# Adafruit_NeoTrellis_4x4.net
KiCad netlist of a schematic drawn in EAGLE
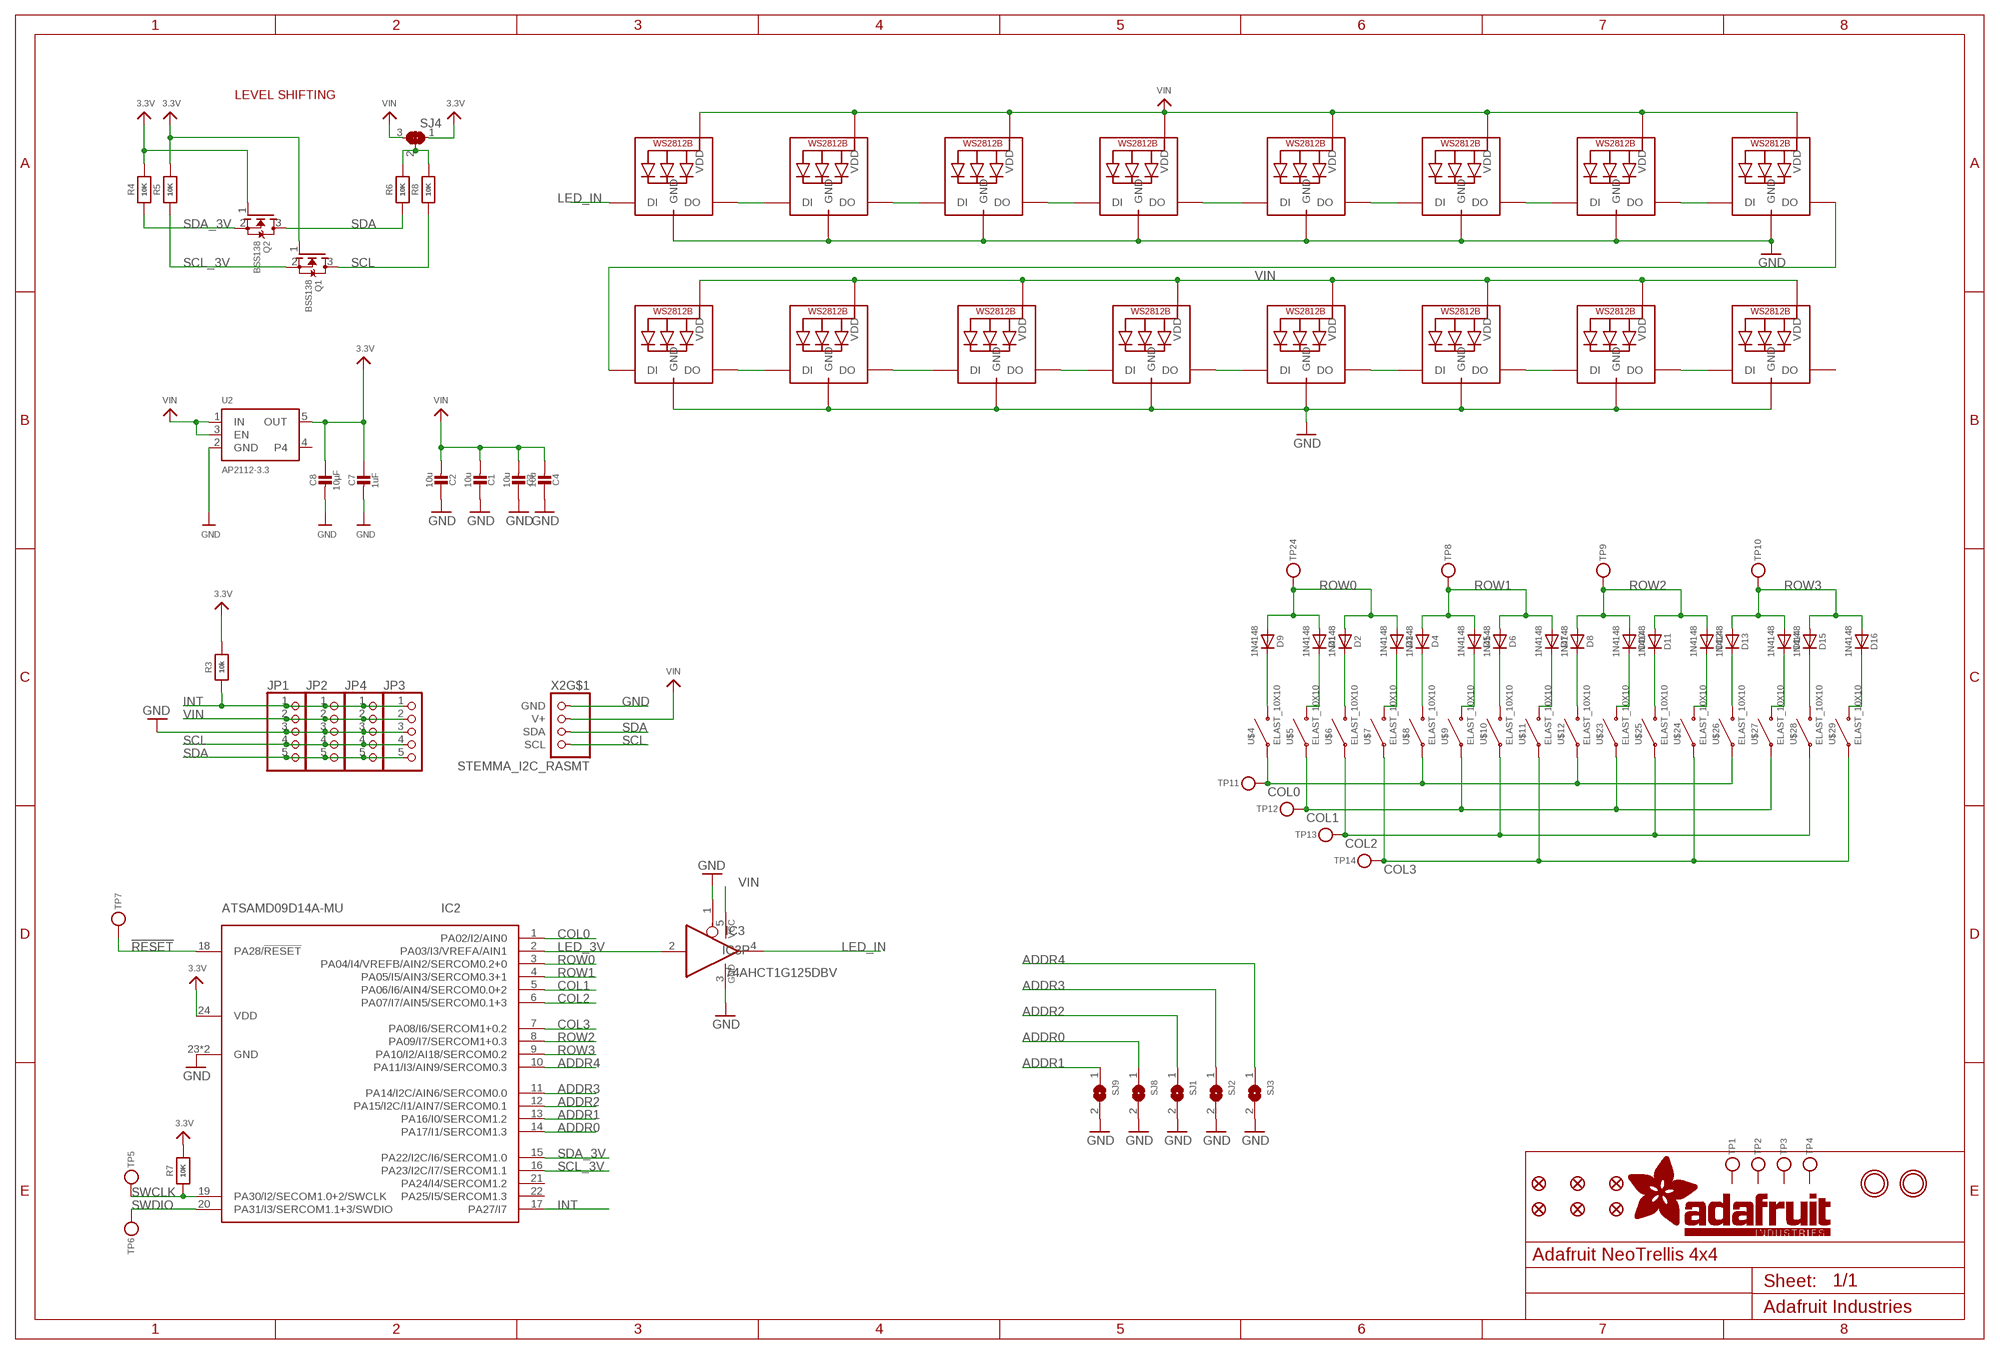
[diagram p0: schematic, sheet 1]

(export (version "E")
  (design (tool "Eeschema 10.0.6"))
  (components
    (comp (ref "C1")
      (value "10u")
      (footprint "eagle-import:0805-NO")
      (libsource (lib "eagle-import") (part "CAP_CERAMIC0805-NOOUTLINE"))
    )
    (comp (ref "C2")
      (value "10u")
      (footprint "eagle-import:0805-NO")
      (libsource (lib "eagle-import") (part "CAP_CERAMIC0805-NOOUTLINE"))
    )
    (comp (ref "C3")
      (value "10u")
      (footprint "eagle-import:0805-NO")
      (libsource (lib "eagle-import") (part "CAP_CERAMIC0805-NOOUTLINE"))
    )
    (comp (ref "C4")
      (value "10u")
      (footprint "eagle-import:0805-NO")
      (libsource (lib "eagle-import") (part "CAP_CERAMIC0805-NOOUTLINE"))
    )
    (comp (ref "C7")
      (value "1uF")
      (footprint "eagle-import:0603-NO")
      (libsource (lib "eagle-import") (part "CAP_CERAMIC0603_NO"))
    )
    (comp (ref "C8")
      (value "10µF")
      (footprint "eagle-import:0805-NO")
      (libsource (lib "eagle-import") (part "CAP_CERAMIC0805-NOOUTLINE"))
    )
    (comp (ref "D1")
      (value "1N4148")
      (footprint "eagle-import:SOD-323")
      (libsource (lib "eagle-import") (part "DIODESOD-323"))
    )
    (comp (ref "D2")
      (value "1N4148")
      (footprint "eagle-import:SOD-323")
      (libsource (lib "eagle-import") (part "DIODESOD-323"))
    )
    (comp (ref "D3")
      (value "1N4148")
      (footprint "eagle-import:SOD-323")
      (libsource (lib "eagle-import") (part "DIODESOD-323"))
    )
    (comp (ref "D4")
      (value "1N4148")
      (footprint "eagle-import:SOD-323")
      (libsource (lib "eagle-import") (part "DIODESOD-323"))
    )
    (comp (ref "D5")
      (value "1N4148")
      (footprint "eagle-import:SOD-323")
      (libsource (lib "eagle-import") (part "DIODESOD-323"))
    )
    (comp (ref "D6")
      (value "1N4148")
      (footprint "eagle-import:SOD-323")
      (libsource (lib "eagle-import") (part "DIODESOD-323"))
    )
    (comp (ref "D7")
      (value "1N4148")
      (footprint "eagle-import:SOD-323")
      (libsource (lib "eagle-import") (part "DIODESOD-323"))
    )
    (comp (ref "D8")
      (value "1N4148")
      (footprint "eagle-import:SOD-323")
      (libsource (lib "eagle-import") (part "DIODESOD-323"))
    )
    (comp (ref "D9")
      (value "1N4148")
      (footprint "eagle-import:SOD-323")
      (libsource (lib "eagle-import") (part "DIODESOD-323"))
    )
    (comp (ref "D10")
      (value "1N4148")
      (footprint "eagle-import:SOD-323")
      (libsource (lib "eagle-import") (part "DIODESOD-323"))
    )
    (comp (ref "D11")
      (value "1N4148")
      (footprint "eagle-import:SOD-323")
      (libsource (lib "eagle-import") (part "DIODESOD-323"))
    )
    (comp (ref "D12")
      (value "1N4148")
      (footprint "eagle-import:SOD-323")
      (libsource (lib "eagle-import") (part "DIODESOD-323"))
    )
    (comp (ref "D13")
      (value "1N4148")
      (footprint "eagle-import:SOD-323")
      (libsource (lib "eagle-import") (part "DIODESOD-323"))
    )
    (comp (ref "D14")
      (value "1N4148")
      (footprint "eagle-import:SOD-323")
      (libsource (lib "eagle-import") (part "DIODESOD-323"))
    )
    (comp (ref "D15")
      (value "1N4148")
      (footprint "eagle-import:SOD-323")
      (libsource (lib "eagle-import") (part "DIODESOD-323"))
    )
    (comp (ref "D16")
      (value "1N4148")
      (footprint "eagle-import:SOD-323")
      (libsource (lib "eagle-import") (part "DIODESOD-323"))
    )
    (comp (ref "FID1")
      (value "FIDUCIAL_1MM")
      (footprint "eagle-import:FIDUCIAL_1MM")
      (libsource (lib "eagle-import") (part "FIDUCIAL_1MM"))
    )
    (comp (ref "FID2")
      (value "FIDUCIAL_1MM")
      (footprint "eagle-import:FIDUCIAL_1MM")
      (libsource (lib "eagle-import") (part "FIDUCIAL_1MM"))
    )
    (comp (ref "FID3")
      (value "FIDUCIAL_1MM")
      (footprint "eagle-import:FIDUCIAL_1MM")
      (libsource (lib "eagle-import") (part "FIDUCIAL_1MM"))
    )
    (comp (ref "FID4")
      (value "FIDUCIAL_1MM")
      (footprint "eagle-import:FIDUCIAL_1MM")
      (libsource (lib "eagle-import") (part "FIDUCIAL_1MM"))
    )
    (comp (ref "FID5")
      (value "FIDUCIAL_1MM")
      (footprint "eagle-import:FIDUCIAL_1MM")
      (libsource (lib "eagle-import") (part "FIDUCIAL_1MM"))
    )
    (comp (ref "FID6")
      (value "FIDUCIAL_1MM")
      (footprint "eagle-import:FIDUCIAL_1MM")
      (libsource (lib "eagle-import") (part "FIDUCIAL_1MM"))
    )
    (comp (ref "IC2")
      (value "ATSAMD09D14A-MU")
      (footprint "eagle-import:QFN24_4MM")
      (libsource (lib "eagle-import") (part "ATSAMD09D14A-MU"))
    )
    (comp (ref "IC3")
      (value "74AHCT1G125DBV")
      (footprint "eagle-import:SOT23-5")
      (libsource (lib "eagle-import") (part "741G125DBVAHCT"))
    )
    (comp (ref "JP1")
      (value "HEADER-1X5EDGESMT")
      (footprint "eagle-import:5P_EDGECONNECT")
      (libsource (lib "eagle-import") (part "HEADER-1X5EDGESMT"))
    )
    (comp (ref "JP2")
      (value "HEADER-1X5EDGESMT")
      (footprint "eagle-import:5P_EDGECONNECT")
      (libsource (lib "eagle-import") (part "HEADER-1X5EDGESMT"))
    )
    (comp (ref "JP3")
      (value "HEADER-1X5EDGESMT")
      (footprint "eagle-import:5P_EDGECONNECT")
      (libsource (lib "eagle-import") (part "HEADER-1X5EDGESMT"))
    )
    (comp (ref "JP4")
      (value "HEADER-1X5EDGESMT")
      (footprint "eagle-import:5P_EDGECONNECT")
      (libsource (lib "eagle-import") (part "HEADER-1X5EDGESMT"))
    )
    (comp (ref "LED1")
      (value "WS2812B3535")
      (footprint "eagle-import:LED3535")
      (libsource (lib "eagle-import") (part "WS2812B3535"))
    )
    (comp (ref "LED2")
      (value "WS2812B3535")
      (footprint "eagle-import:LED3535")
      (libsource (lib "eagle-import") (part "WS2812B3535"))
    )
    (comp (ref "LED3")
      (value "WS2812B3535")
      (footprint "eagle-import:LED3535")
      (libsource (lib "eagle-import") (part "WS2812B3535"))
    )
    (comp (ref "LED4")
      (value "WS2812B3535")
      (footprint "eagle-import:LED3535")
      (libsource (lib "eagle-import") (part "WS2812B3535"))
    )
    (comp (ref "LED5")
      (value "WS2812B3535")
      (footprint "eagle-import:LED3535")
      (libsource (lib "eagle-import") (part "WS2812B3535"))
    )
    (comp (ref "LED6")
      (value "WS2812B3535")
      (footprint "eagle-import:LED3535")
      (libsource (lib "eagle-import") (part "WS2812B3535"))
    )
    (comp (ref "LED7")
      (value "WS2812B3535")
      (footprint "eagle-import:LED3535")
      (libsource (lib "eagle-import") (part "WS2812B3535"))
    )
    (comp (ref "LED8")
      (value "WS2812B3535")
      (footprint "eagle-import:LED3535")
      (libsource (lib "eagle-import") (part "WS2812B3535"))
    )
    (comp (ref "LED9")
      (value "WS2812B3535")
      (footprint "eagle-import:LED3535")
      (libsource (lib "eagle-import") (part "WS2812B3535"))
    )
    (comp (ref "LED10")
      (value "WS2812B3535")
      (footprint "eagle-import:LED3535")
      (libsource (lib "eagle-import") (part "WS2812B3535"))
    )
    (comp (ref "LED11")
      (value "WS2812B3535")
      (footprint "eagle-import:LED3535")
      (libsource (lib "eagle-import") (part "WS2812B3535"))
    )
    (comp (ref "LED12")
      (value "WS2812B3535")
      (footprint "eagle-import:LED3535")
      (libsource (lib "eagle-import") (part "WS2812B3535"))
    )
    (comp (ref "LED13")
      (value "WS2812B3535")
      (footprint "eagle-import:LED3535")
      (libsource (lib "eagle-import") (part "WS2812B3535"))
    )
    (comp (ref "LED14")
      (value "WS2812B3535")
      (footprint "eagle-import:LED3535")
      (libsource (lib "eagle-import") (part "WS2812B3535"))
    )
    (comp (ref "LED15")
      (value "WS2812B3535")
      (footprint "eagle-import:LED3535")
      (libsource (lib "eagle-import") (part "WS2812B3535"))
    )
    (comp (ref "LED16")
      (value "WS2812B3535")
      (footprint "eagle-import:LED3535")
      (libsource (lib "eagle-import") (part "WS2812B3535"))
    )
    (comp (ref "Q1")
      (value "BSS138")
      (footprint "eagle-import:SOT23-WIDE")
      (libsource (lib "eagle-import") (part "MOSFET-NWIDE"))
    )
    (comp (ref "Q2")
      (value "BSS138")
      (footprint "eagle-import:SOT23-WIDE")
      (libsource (lib "eagle-import") (part "MOSFET-NWIDE"))
    )
    (comp (ref "R3")
      (value "10k")
      (footprint "eagle-import:0603-NO")
      (libsource (lib "eagle-import") (part "RESISTOR_0603_NOOUT"))
    )
    (comp (ref "R4")
      (value "10K")
      (footprint "eagle-import:0603-NO")
      (libsource (lib "eagle-import") (part "RESISTOR_0603_NOOUT"))
    )
    (comp (ref "R5")
      (value "10K")
      (footprint "eagle-import:0603-NO")
      (libsource (lib "eagle-import") (part "RESISTOR_0603_NOOUT"))
    )
    (comp (ref "R6")
      (value "10K")
      (footprint "eagle-import:0603-NO")
      (libsource (lib "eagle-import") (part "RESISTOR_0603_NOOUT"))
    )
    (comp (ref "R7")
      (value "10K")
      (footprint "eagle-import:0603-NO")
      (libsource (lib "eagle-import") (part "RESISTOR_0603_NOOUT"))
    )
    (comp (ref "R8")
      (value "10K")
      (footprint "eagle-import:0603-NO")
      (libsource (lib "eagle-import") (part "RESISTOR_0603_NOOUT"))
    )
    (comp (ref "SJ1")
      (value "SOLDERJUMPER")
      (footprint "eagle-import:SOLDERJUMPER_ARROW_NOPASTE")
      (libsource (lib "eagle-import") (part "SOLDERJUMPER"))
    )
    (comp (ref "SJ2")
      (value "SOLDERJUMPER")
      (footprint "eagle-import:SOLDERJUMPER_ARROW_NOPASTE")
      (libsource (lib "eagle-import") (part "SOLDERJUMPER"))
    )
    (comp (ref "SJ3")
      (value "SOLDERJUMPER")
      (footprint "eagle-import:SOLDERJUMPER_ARROW_NOPASTE")
      (libsource (lib "eagle-import") (part "SOLDERJUMPER"))
    )
    (comp (ref "SJ4")
      (value "SOLDERJUMPER_2WAY")
      (footprint "eagle-import:SOLDERJUMPER_2WAY_OPEN_NOPASTE")
      (libsource (lib "eagle-import") (part "SOLDERJUMPER_2WAY"))
    )
    (comp (ref "SJ8")
      (value "SOLDERJUMPER")
      (footprint "eagle-import:SOLDERJUMPER_ARROW_NOPASTE")
      (libsource (lib "eagle-import") (part "SOLDERJUMPER"))
    )
    (comp (ref "SJ9")
      (value "SOLDERJUMPER")
      (footprint "eagle-import:SOLDERJUMPER_ARROW_NOPASTE")
      (libsource (lib "eagle-import") (part "SOLDERJUMPER"))
    )
    (comp (ref "TP1")
      (value "TESTPOINT")
      (footprint "eagle-import:TESTPOINT_SMT")
      (libsource (lib "eagle-import") (part "TESTPOINT"))
    )
    (comp (ref "TP2")
      (value "TESTPOINT")
      (footprint "eagle-import:TESTPOINT_SMT")
      (libsource (lib "eagle-import") (part "TESTPOINT"))
    )
    (comp (ref "TP3")
      (value "TESTPOINT")
      (footprint "eagle-import:TESTPOINT_SMT")
      (libsource (lib "eagle-import") (part "TESTPOINT"))
    )
    (comp (ref "TP4")
      (value "TESTPOINT")
      (footprint "eagle-import:TESTPOINT_SMT")
      (libsource (lib "eagle-import") (part "TESTPOINT"))
    )
    (comp (ref "TP5")
      (value "TESTPOINTROUND2MM")
      (footprint "eagle-import:TESTPOINT_ROUND_2MM")
      (libsource (lib "eagle-import") (part "TESTPOINTROUND2MM"))
    )
    (comp (ref "TP6")
      (value "TESTPOINTROUND2MM")
      (footprint "eagle-import:TESTPOINT_ROUND_2MM")
      (libsource (lib "eagle-import") (part "TESTPOINTROUND2MM"))
    )
    (comp (ref "TP7")
      (value "TESTPOINTROUND1.5MM")
      (footprint "eagle-import:TESTPOINT_ROUND_1.5MM")
      (libsource (lib "eagle-import") (part "TESTPOINTROUND1.5MM"))
    )
    (comp (ref "TP8")
      (value "TESTPOINTROUND1.5MM")
      (footprint "eagle-import:TESTPOINT_ROUND_1.5MM")
      (libsource (lib "eagle-import") (part "TESTPOINTROUND1.5MM"))
    )
    (comp (ref "TP9")
      (value "TESTPOINTROUND1.5MM")
      (footprint "eagle-import:TESTPOINT_ROUND_1.5MM")
      (libsource (lib "eagle-import") (part "TESTPOINTROUND1.5MM"))
    )
    (comp (ref "TP10")
      (value "TESTPOINTROUND1.5MM")
      (footprint "eagle-import:TESTPOINT_ROUND_1.5MM")
      (libsource (lib "eagle-import") (part "TESTPOINTROUND1.5MM"))
    )
    (comp (ref "TP11")
      (value "TESTPOINTROUND1.5MM")
      (footprint "eagle-import:TESTPOINT_ROUND_1.5MM")
      (libsource (lib "eagle-import") (part "TESTPOINTROUND1.5MM"))
    )
    (comp (ref "TP12")
      (value "TESTPOINTROUND1.5MM")
      (footprint "eagle-import:TESTPOINT_ROUND_1.5MM")
      (libsource (lib "eagle-import") (part "TESTPOINTROUND1.5MM"))
    )
    (comp (ref "TP13")
      (value "TESTPOINTROUND1.5MM")
      (footprint "eagle-import:TESTPOINT_ROUND_1.5MM")
      (libsource (lib "eagle-import") (part "TESTPOINTROUND1.5MM"))
    )
    (comp (ref "TP14")
      (value "TESTPOINTROUND1.5MM")
      (footprint "eagle-import:TESTPOINT_ROUND_1.5MM")
      (libsource (lib "eagle-import") (part "TESTPOINTROUND1.5MM"))
    )
    (comp (ref "TP24")
      (value "TESTPOINTROUND1.5MM")
      (footprint "eagle-import:TESTPOINT_ROUND_1.5MM")
      (libsource (lib "eagle-import") (part "TESTPOINTROUND1.5MM"))
    )
    (comp (ref "U$1")
      (value "MOUNTINGHOLE2.5")
      (footprint "eagle-import:MOUNTINGHOLE_2.5_PLATED")
      (libsource (lib "eagle-import") (part "MOUNTINGHOLE2.5"))
    )
    (comp (ref "U$2")
      (value "MOUNTINGHOLE2.5")
      (footprint "eagle-import:MOUNTINGHOLE_2.5_PLATED")
      (libsource (lib "eagle-import") (part "MOUNTINGHOLE2.5"))
    )
    (comp (ref "U$4")
      (value "ELAST_10X10")
      (footprint "eagle-import:ELAST_PAD_SQUARE_10MM_4X4WIDE")
      (libsource (lib "eagle-import") (part "ELAST_10X10"))
    )
    (comp (ref "U$5")
      (value "ELAST_10X10")
      (footprint "eagle-import:ELAST_PAD_SQUARE_10MM_4X4WIDE")
      (libsource (lib "eagle-import") (part "ELAST_10X10"))
    )
    (comp (ref "U$6")
      (value "ELAST_10X10")
      (footprint "eagle-import:ELAST_PAD_SQUARE_10MM_4X4WIDE")
      (libsource (lib "eagle-import") (part "ELAST_10X10"))
    )
    (comp (ref "U$7")
      (value "ELAST_10X10")
      (footprint "eagle-import:ELAST_PAD_SQUARE_10MM_4X4WIDE")
      (libsource (lib "eagle-import") (part "ELAST_10X10"))
    )
    (comp (ref "U$8")
      (value "ELAST_10X10")
      (footprint "eagle-import:ELAST_PAD_SQUARE_10MM_4X4WIDE")
      (libsource (lib "eagle-import") (part "ELAST_10X10"))
    )
    (comp (ref "U$9")
      (value "ELAST_10X10")
      (footprint "eagle-import:ELAST_PAD_SQUARE_10MM_4X4WIDE")
      (libsource (lib "eagle-import") (part "ELAST_10X10"))
    )
    (comp (ref "U$10")
      (value "ELAST_10X10")
      (footprint "eagle-import:ELAST_PAD_SQUARE_10MM_4X4WIDE")
      (libsource (lib "eagle-import") (part "ELAST_10X10"))
    )
    (comp (ref "U$11")
      (value "ELAST_10X10")
      (footprint "eagle-import:ELAST_PAD_SQUARE_10MM_4X4WIDE")
      (libsource (lib "eagle-import") (part "ELAST_10X10"))
    )
    (comp (ref "U$12")
      (value "ELAST_10X10")
      (footprint "eagle-import:ELAST_PAD_SQUARE_10MM_4X4WIDE")
      (libsource (lib "eagle-import") (part "ELAST_10X10"))
    )
    (comp (ref "U$23")
      (value "ELAST_10X10")
      (footprint "eagle-import:ELAST_PAD_SQUARE_10MM_4X4WIDE")
      (libsource (lib "eagle-import") (part "ELAST_10X10"))
    )
    (comp (ref "U$24")
      (value "ELAST_10X10")
      (footprint "eagle-import:ELAST_PAD_SQUARE_10MM_4X4WIDE")
      (libsource (lib "eagle-import") (part "ELAST_10X10"))
    )
    (comp (ref "U$25")
      (value "ELAST_10X10")
      (footprint "eagle-import:ELAST_PAD_SQUARE_10MM_4X4WIDE")
      (libsource (lib "eagle-import") (part "ELAST_10X10"))
    )
    (comp (ref "U$26")
      (value "ELAST_10X10")
      (footprint "eagle-import:ELAST_PAD_SQUARE_10MM_4X4WIDE")
      (libsource (lib "eagle-import") (part "ELAST_10X10"))
    )
    (comp (ref "U$27")
      (value "ELAST_10X10")
      (footprint "eagle-import:ELAST_PAD_SQUARE_10MM_4X4WIDE")
      (libsource (lib "eagle-import") (part "ELAST_10X10"))
    )
    (comp (ref "U$28")
      (value "ELAST_10X10")
      (footprint "eagle-import:ELAST_PAD_SQUARE_10MM_4X4WIDE")
      (libsource (lib "eagle-import") (part "ELAST_10X10"))
    )
    (comp (ref "U$29")
      (value "ELAST_10X10")
      (footprint "eagle-import:ELAST_PAD_SQUARE_10MM_4X4WIDE")
      (libsource (lib "eagle-import") (part "ELAST_10X10"))
    )
    (comp (ref "U2")
      (value "AP2112-3.3")
      (footprint "eagle-import:SOT23-5")
      (libsource (lib "eagle-import") (part "VREG_SOT23-5"))
    )
    (comp (ref "X2")
      (value "STEMMA_I2C_RASMT")
      (footprint "eagle-import:JSTPH4")
      (libsource (lib "eagle-import") (part "STEMMA_I2C_RASMT"))
    )
  )
  (nets
    (net (code "1") (name "/ADDR0") (class "Default")
      (node (ref "IC2") (pin "14") (pinfunction "PA17/I1/SERCOM1.3_14") (pintype "bidirectional"))
      (node (ref "SJ8") (pin "1") (pinfunction "1_1") (pintype "passive"))
    )
    (net (code "2") (name "/ADDR1") (class "Default")
      (node (ref "IC2") (pin "13") (pinfunction "PA16/I0/SERCOM1.2_13") (pintype "bidirectional"))
      (node (ref "SJ9") (pin "1") (pinfunction "1_1") (pintype "passive"))
    )
    (net (code "3") (name "/ADDR2") (class "Default")
      (node (ref "IC2") (pin "12") (pinfunction "PA15/I2C/I1/AIN7/SERCOM0.1_12") (pintype "bidirectional"))
      (node (ref "SJ1") (pin "1") (pinfunction "1_1") (pintype "passive"))
    )
    (net (code "4") (name "/ADDR3") (class "Default")
      (node (ref "IC2") (pin "11") (pinfunction "PA14/I2C/AIN6/SERCOM0.0_11") (pintype "bidirectional"))
      (node (ref "SJ2") (pin "1") (pinfunction "1_1") (pintype "passive"))
    )
    (net (code "5") (name "/ADDR4") (class "Default")
      (node (ref "IC2") (pin "10") (pinfunction "PA11/I3/AIN9/SERCOM0.3_10") (pintype "bidirectional"))
      (node (ref "SJ3") (pin "1") (pinfunction "1_1") (pintype "passive"))
    )
    (net (code "6") (name "/COL0") (class "Default")
      (node (ref "IC2") (pin "1") (pinfunction "PA02/I2/AIN0_1") (pintype "bidirectional"))
      (node (ref "TP11") (pin "P$1") (pinfunction "P$1_P$1") (pintype "bidirectional"))
      (node (ref "U$12") (pin "P$1") (pinfunction "P$1_P$1") (pintype "bidirectional"))
      (node (ref "U$26") (pin "P$1") (pinfunction "P$1_P$1") (pintype "bidirectional"))
      (node (ref "U$4") (pin "P$1") (pinfunction "P$1_P$1") (pintype "bidirectional"))
      (node (ref "U$8") (pin "P$1") (pinfunction "P$1_P$1") (pintype "bidirectional"))
    )
    (net (code "7") (name "/COL1") (class "Default")
      (node (ref "IC2") (pin "5") (pinfunction "PA06/I6/AIN4/SERCOM0.0+2_5") (pintype "bidirectional"))
      (node (ref "TP12") (pin "P$1") (pinfunction "P$1_P$1") (pintype "bidirectional"))
      (node (ref "U$23") (pin "P$1") (pinfunction "P$1_P$1") (pintype "bidirectional"))
      (node (ref "U$27") (pin "P$1") (pinfunction "P$1_P$1") (pintype "bidirectional"))
      (node (ref "U$5") (pin "P$1") (pinfunction "P$1_P$1") (pintype "bidirectional"))
      (node (ref "U$9") (pin "P$1") (pinfunction "P$1_P$1") (pintype "bidirectional"))
    )
    (net (code "8") (name "/COL2") (class "Default")
      (node (ref "IC2") (pin "6") (pinfunction "PA07/I7/AIN5/SERCOM0.1+3_6") (pintype "bidirectional"))
      (node (ref "TP13") (pin "P$1") (pinfunction "P$1_P$1") (pintype "bidirectional"))
      (node (ref "U$10") (pin "P$1") (pinfunction "P$1_P$1") (pintype "bidirectional"))
      (node (ref "U$25") (pin "P$1") (pinfunction "P$1_P$1") (pintype "bidirectional"))
      (node (ref "U$28") (pin "P$1") (pinfunction "P$1_P$1") (pintype "bidirectional"))
      (node (ref "U$6") (pin "P$1") (pinfunction "P$1_P$1") (pintype "bidirectional"))
    )
    (net (code "9") (name "/COL3") (class "Default")
      (node (ref "IC2") (pin "7") (pinfunction "PA08/I6/SERCOM1+0.2_7") (pintype "bidirectional"))
      (node (ref "TP14") (pin "P$1") (pinfunction "P$1_P$1") (pintype "bidirectional"))
      (node (ref "U$11") (pin "P$1") (pinfunction "P$1_P$1") (pintype "bidirectional"))
      (node (ref "U$24") (pin "P$1") (pinfunction "P$1_P$1") (pintype "bidirectional"))
      (node (ref "U$29") (pin "P$1") (pinfunction "P$1_P$1") (pintype "bidirectional"))
      (node (ref "U$7") (pin "P$1") (pinfunction "P$1_P$1") (pintype "bidirectional"))
    )
    (net (code "10") (name "/INT") (class "Default")
      (node (ref "IC2") (pin "17") (pinfunction "PA27/I7_17") (pintype "bidirectional"))
      (node (ref "JP1") (pin "1") (pinfunction "1_1") (pintype "passive"))
      (node (ref "JP2") (pin "1") (pinfunction "1_1") (pintype "passive"))
      (node (ref "JP3") (pin "1") (pinfunction "1_1") (pintype "passive"))
      (node (ref "JP4") (pin "1") (pinfunction "1_1") (pintype "passive"))
      (node (ref "R3") (pin "1") (pinfunction "1_1") (pintype "passive"))
    )
    (net (code "11") (name "/LED_3V") (class "Default")
      (node (ref "IC2") (pin "2") (pinfunction "PA03/I3/VREFA/AIN1_2") (pintype "bidirectional"))
      (node (ref "IC3") (pin "2") (pinfunction "I_2") (pintype "input"))
    )
    (net (code "12") (name "/LED_IN") (class "Default")
      (node (ref "IC3") (pin "4") (pinfunction "O_4") (pintype "tri_state"))
      (node (ref "LED1") (pin "1") (pinfunction "DI_1") (pintype "input"))
    )
    (net (code "13") (name "/ROW0") (class "Default")
      (node (ref "D1") (pin "A") (pinfunction "A_A") (pintype "passive"))
      (node (ref "D2") (pin "A") (pinfunction "A_A") (pintype "passive"))
      (node (ref "D3") (pin "A") (pinfunction "A_A") (pintype "passive"))
      (node (ref "D9") (pin "A") (pinfunction "A_A") (pintype "passive"))
      (node (ref "IC2") (pin "3") (pinfunction "PA04/I4/VREFB/AIN2/SERCOM0.2+0_3") (pintype "bidirectional"))
      (node (ref "TP24") (pin "P$1") (pinfunction "P$1_P$1") (pintype "bidirectional"))
    )
    (net (code "14") (name "/ROW1") (class "Default")
      (node (ref "D4") (pin "A") (pinfunction "A_A") (pintype "passive"))
      (node (ref "D5") (pin "A") (pinfunction "A_A") (pintype "passive"))
      (node (ref "D6") (pin "A") (pinfunction "A_A") (pintype "passive"))
      (node (ref "D7") (pin "A") (pinfunction "A_A") (pintype "passive"))
      (node (ref "IC2") (pin "4") (pinfunction "PA05/I5/AIN3/SERCOM0.3+1_4") (pintype "bidirectional"))
      (node (ref "TP8") (pin "P$1") (pinfunction "P$1_P$1") (pintype "bidirectional"))
    )
    (net (code "15") (name "/ROW2") (class "Default")
      (node (ref "D10") (pin "A") (pinfunction "A_A") (pintype "passive"))
      (node (ref "D11") (pin "A") (pinfunction "A_A") (pintype "passive"))
      (node (ref "D12") (pin "A") (pinfunction "A_A") (pintype "passive"))
      (node (ref "D8") (pin "A") (pinfunction "A_A") (pintype "passive"))
      (node (ref "IC2") (pin "8") (pinfunction "PA09/I7/SERCOM1+0.3_8") (pintype "bidirectional"))
      (node (ref "TP9") (pin "P$1") (pinfunction "P$1_P$1") (pintype "bidirectional"))
    )
    (net (code "16") (name "/ROW3") (class "Default")
      (node (ref "D13") (pin "A") (pinfunction "A_A") (pintype "passive"))
      (node (ref "D14") (pin "A") (pinfunction "A_A") (pintype "passive"))
      (node (ref "D15") (pin "A") (pinfunction "A_A") (pintype "passive"))
      (node (ref "D16") (pin "A") (pinfunction "A_A") (pintype "passive"))
      (node (ref "IC2") (pin "9") (pinfunction "PA10/I2/AI18/SERCOM0.2_9") (pintype "bidirectional"))
      (node (ref "TP10") (pin "P$1") (pinfunction "P$1_P$1") (pintype "bidirectional"))
    )
    (net (code "17") (name "/SCL") (class "Default")
      (node (ref "JP1") (pin "4") (pinfunction "4_4") (pintype "passive"))
      (node (ref "JP2") (pin "4") (pinfunction "4_4") (pintype "passive"))
      (node (ref "JP3") (pin "4") (pinfunction "4_4") (pintype "passive"))
      (node (ref "JP4") (pin "4") (pinfunction "4_4") (pintype "passive"))
      (node (ref "Q1") (pin "3") (pinfunction "D_3") (pintype "bidirectional"))
      (node (ref "R8") (pin "1") (pinfunction "1_1") (pintype "passive"))
      (node (ref "X2") (pin "4") (pinfunction "SCL_4") (pintype "passive"))
    )
    (net (code "18") (name "/SCL_3V") (class "Default")
      (node (ref "IC2") (pin "16") (pinfunction "PA23/I2C/I7/SERCOM1.1_16") (pintype "bidirectional"))
      (node (ref "Q1") (pin "2") (pinfunction "S_2") (pintype "bidirectional"))
      (node (ref "R5") (pin "1") (pinfunction "1_1") (pintype "passive"))
    )
    (net (code "19") (name "/SDA") (class "Default")
      (node (ref "JP1") (pin "5") (pinfunction "5_5") (pintype "passive"))
      (node (ref "JP2") (pin "5") (pinfunction "5_5") (pintype "passive"))
      (node (ref "JP3") (pin "5") (pinfunction "5_5") (pintype "passive"))
      (node (ref "JP4") (pin "5") (pinfunction "5_5") (pintype "passive"))
      (node (ref "Q2") (pin "3") (pinfunction "D_3") (pintype "bidirectional"))
      (node (ref "R6") (pin "1") (pinfunction "1_1") (pintype "passive"))
      (node (ref "X2") (pin "3") (pinfunction "SDA_3") (pintype "passive"))
    )
    (net (code "20") (name "/SDA_3V") (class "Default")
      (node (ref "IC2") (pin "15") (pinfunction "PA22/I2C/I6/SERCOM1.0_15") (pintype "bidirectional"))
      (node (ref "Q2") (pin "2") (pinfunction "S_2") (pintype "bidirectional"))
      (node (ref "R4") (pin "1") (pinfunction "1_1") (pintype "passive"))
    )
    (net (code "21") (name "/SWCLK") (class "Default")
      (node (ref "IC2") (pin "19") (pinfunction "PA30/I2/SECOM1.0+2/SWCLK_19") (pintype "bidirectional"))
      (node (ref "R7") (pin "1") (pinfunction "1_1") (pintype "passive"))
      (node (ref "TP5") (pin "P$1") (pinfunction "P$1_P$1") (pintype "bidirectional"))
    )
    (net (code "22") (name "/SWDIO") (class "Default")
      (node (ref "IC2") (pin "20") (pinfunction "PA31/I3/SERCOM1.1+3/SWDIO_20") (pintype "bidirectional"))
      (node (ref "TP6") (pin "P$1") (pinfunction "P$1_P$1") (pintype "bidirectional"))
    )
    (net (code "23") (name "/~{RESET}") (class "Default")
      (node (ref "IC2") (pin "18") (pinfunction "PA28/~{RESET}_18") (pintype "bidirectional"))
      (node (ref "TP7") (pin "P$1") (pinfunction "P$1_P$1") (pintype "bidirectional"))
    )
    (net (code "24") (name "3.3V") (class "Default")
      (node (ref "C7") (pin "1") (pinfunction "1_1") (pintype "passive"))
      (node (ref "C8") (pin "1") (pinfunction "1_1") (pintype "passive"))
      (node (ref "IC2") (pin "24") (pinfunction "VDD_24") (pintype "power_in"))
      (node (ref "Q1") (pin "1") (pinfunction "G_1") (pintype "bidirectional"))
      (node (ref "Q2") (pin "1") (pinfunction "G_1") (pintype "bidirectional"))
      (node (ref "R3") (pin "2") (pinfunction "2_2") (pintype "passive"))
      (node (ref "R4") (pin "2") (pinfunction "2_2") (pintype "passive"))
      (node (ref "R5") (pin "2") (pinfunction "2_2") (pintype "passive"))
      (node (ref "R7") (pin "2") (pinfunction "2_2") (pintype "passive"))
      (node (ref "SJ4") (pin "1") (pinfunction "1_1") (pintype "passive"))
      (node (ref "U2") (pin "5") (pinfunction "OUT_5") (pintype "power_in"))
    )
    (net (code "25") (name "GND") (class "Default")
      (node (ref "C1") (pin "1") (pinfunction "1_1") (pintype "passive"))
      (node (ref "C2") (pin "1") (pinfunction "1_1") (pintype "passive"))
      (node (ref "C3") (pin "1") (pinfunction "1_1") (pintype "passive"))
      (node (ref "C4") (pin "1") (pinfunction "1_1") (pintype "passive"))
      (node (ref "C7") (pin "2") (pinfunction "2_2") (pintype "passive"))
      (node (ref "C8") (pin "2") (pinfunction "2_2") (pintype "passive"))
      (node (ref "IC2") (pin "23") (pinfunction "GND_23") (pintype "power_in"))
      (node (ref "IC2") (pin "THERM") (pinfunction "GND_THERM") (pintype "power_in"))
      (node (ref "IC3") (pin "1") (pinfunction "OE_1") (pintype "input"))
      (node (ref "IC3") (pin "3") (pinfunction "GND_3") (pintype "power_in"))
      (node (ref "JP1") (pin "3") (pinfunction "3_3") (pintype "passive"))
      (node (ref "JP2") (pin "3") (pinfunction "3_3") (pintype "passive"))
      (node (ref "JP3") (pin "3") (pinfunction "3_3") (pintype "passive"))
      (node (ref "JP4") (pin "3") (pinfunction "3_3") (pintype "passive"))
      (node (ref "LED1") (pin "4") (pinfunction "GND_4") (pintype "power_in"))
      (node (ref "LED10") (pin "4") (pinfunction "GND_4") (pintype "power_in"))
      (node (ref "LED11") (pin "4") (pinfunction "GND_4") (pintype "power_in"))
      (node (ref "LED12") (pin "4") (pinfunction "GND_4") (pintype "power_in"))
      (node (ref "LED13") (pin "4") (pinfunction "GND_4") (pintype "power_in"))
      (node (ref "LED14") (pin "4") (pinfunction "GND_4") (pintype "power_in"))
      (node (ref "LED15") (pin "4") (pinfunction "GND_4") (pintype "power_in"))
      (node (ref "LED16") (pin "4") (pinfunction "GND_4") (pintype "power_in"))
      (node (ref "LED2") (pin "4") (pinfunction "GND_4") (pintype "power_in"))
      (node (ref "LED3") (pin "4") (pinfunction "GND_4") (pintype "power_in"))
      (node (ref "LED4") (pin "4") (pinfunction "GND_4") (pintype "power_in"))
      (node (ref "LED5") (pin "4") (pinfunction "GND_4") (pintype "power_in"))
      (node (ref "LED6") (pin "4") (pinfunction "GND_4") (pintype "power_in"))
      (node (ref "LED7") (pin "4") (pinfunction "GND_4") (pintype "power_in"))
      (node (ref "LED8") (pin "4") (pinfunction "GND_4") (pintype "power_in"))
      (node (ref "LED9") (pin "4") (pinfunction "GND_4") (pintype "power_in"))
      (node (ref "SJ1") (pin "2") (pinfunction "2_2") (pintype "passive"))
      (node (ref "SJ2") (pin "2") (pinfunction "2_2") (pintype "passive"))
      (node (ref "SJ3") (pin "2") (pinfunction "2_2") (pintype "passive"))
      (node (ref "SJ8") (pin "2") (pinfunction "2_2") (pintype "passive"))
      (node (ref "SJ9") (pin "2") (pinfunction "2_2") (pintype "passive"))
      (node (ref "U2") (pin "2") (pinfunction "GND_2") (pintype "power_in"))
      (node (ref "X2") (pin "1") (pinfunction "GND_1") (pintype "passive"))
    )
    (net (code "26") (name "Net-(D1-PadC)") (class "Default")
      (node (ref "D1") (pin "C") (pinfunction "C_C") (pintype "passive"))
      (node (ref "U$5") (pin "P$2") (pinfunction "P$2_P$2") (pintype "bidirectional"))
    )
    (net (code "27") (name "Net-(D2-PadC)") (class "Default")
      (node (ref "D2") (pin "C") (pinfunction "C_C") (pintype "passive"))
      (node (ref "U$6") (pin "P$2") (pinfunction "P$2_P$2") (pintype "bidirectional"))
    )
    (net (code "28") (name "Net-(D3-PadC)") (class "Default")
      (node (ref "D3") (pin "C") (pinfunction "C_C") (pintype "passive"))
      (node (ref "U$7") (pin "P$2") (pinfunction "P$2_P$2") (pintype "bidirectional"))
    )
    (net (code "29") (name "Net-(D4-PadC)") (class "Default")
      (node (ref "D4") (pin "C") (pinfunction "C_C") (pintype "passive"))
      (node (ref "U$8") (pin "P$2") (pinfunction "P$2_P$2") (pintype "bidirectional"))
    )
    (net (code "30") (name "Net-(D5-PadC)") (class "Default")
      (node (ref "D5") (pin "C") (pinfunction "C_C") (pintype "passive"))
      (node (ref "U$9") (pin "P$2") (pinfunction "P$2_P$2") (pintype "bidirectional"))
    )
    (net (code "31") (name "Net-(D6-PadC)") (class "Default")
      (node (ref "D6") (pin "C") (pinfunction "C_C") (pintype "passive"))
      (node (ref "U$10") (pin "P$2") (pinfunction "P$2_P$2") (pintype "bidirectional"))
    )
    (net (code "32") (name "Net-(D7-PadC)") (class "Default")
      (node (ref "D7") (pin "C") (pinfunction "C_C") (pintype "passive"))
      (node (ref "U$11") (pin "P$2") (pinfunction "P$2_P$2") (pintype "bidirectional"))
    )
    (net (code "33") (name "Net-(D8-PadC)") (class "Default")
      (node (ref "D8") (pin "C") (pinfunction "C_C") (pintype "passive"))
      (node (ref "U$12") (pin "P$2") (pinfunction "P$2_P$2") (pintype "bidirectional"))
    )
    (net (code "34") (name "Net-(D9-PadC)") (class "Default")
      (node (ref "D9") (pin "C") (pinfunction "C_C") (pintype "passive"))
      (node (ref "U$4") (pin "P$2") (pinfunction "P$2_P$2") (pintype "bidirectional"))
    )
    (net (code "35") (name "Net-(D10-PadC)") (class "Default")
      (node (ref "D10") (pin "C") (pinfunction "C_C") (pintype "passive"))
      (node (ref "U$23") (pin "P$2") (pinfunction "P$2_P$2") (pintype "bidirectional"))
    )
    (net (code "36") (name "Net-(D11-PadC)") (class "Default")
      (node (ref "D11") (pin "C") (pinfunction "C_C") (pintype "passive"))
      (node (ref "U$25") (pin "P$2") (pinfunction "P$2_P$2") (pintype "bidirectional"))
    )
    (net (code "37") (name "Net-(D12-PadC)") (class "Default")
      (node (ref "D12") (pin "C") (pinfunction "C_C") (pintype "passive"))
      (node (ref "U$24") (pin "P$2") (pinfunction "P$2_P$2") (pintype "bidirectional"))
    )
    (net (code "38") (name "Net-(D13-PadC)") (class "Default")
      (node (ref "D13") (pin "C") (pinfunction "C_C") (pintype "passive"))
      (node (ref "U$26") (pin "P$2") (pinfunction "P$2_P$2") (pintype "bidirectional"))
    )
    (net (code "39") (name "Net-(D14-PadC)") (class "Default")
      (node (ref "D14") (pin "C") (pinfunction "C_C") (pintype "passive"))
      (node (ref "U$27") (pin "P$2") (pinfunction "P$2_P$2") (pintype "bidirectional"))
    )
    (net (code "40") (name "Net-(D15-PadC)") (class "Default")
      (node (ref "D15") (pin "C") (pinfunction "C_C") (pintype "passive"))
      (node (ref "U$28") (pin "P$2") (pinfunction "P$2_P$2") (pintype "bidirectional"))
    )
    (net (code "41") (name "Net-(D16-PadC)") (class "Default")
      (node (ref "D16") (pin "C") (pinfunction "C_C") (pintype "passive"))
      (node (ref "U$29") (pin "P$2") (pinfunction "P$2_P$2") (pintype "bidirectional"))
    )
    (net (code "42") (name "Net-(LED1-DO)") (class "Default")
      (node (ref "LED1") (pin "3") (pinfunction "DO_3") (pintype "output"))
      (node (ref "LED2") (pin "1") (pinfunction "DI_1") (pintype "input"))
    )
    (net (code "43") (name "Net-(LED2-DO)") (class "Default")
      (node (ref "LED2") (pin "3") (pinfunction "DO_3") (pintype "output"))
      (node (ref "LED3") (pin "1") (pinfunction "DI_1") (pintype "input"))
    )
    (net (code "44") (name "Net-(LED3-DO)") (class "Default")
      (node (ref "LED3") (pin "3") (pinfunction "DO_3") (pintype "output"))
      (node (ref "LED4") (pin "1") (pinfunction "DI_1") (pintype "input"))
    )
    (net (code "45") (name "Net-(LED4-DO)") (class "Default")
      (node (ref "LED4") (pin "3") (pinfunction "DO_3") (pintype "output"))
      (node (ref "LED5") (pin "1") (pinfunction "DI_1") (pintype "input"))
    )
    (net (code "46") (name "Net-(LED5-DO)") (class "Default")
      (node (ref "LED5") (pin "3") (pinfunction "DO_3") (pintype "output"))
      (node (ref "LED6") (pin "1") (pinfunction "DI_1") (pintype "input"))
    )
    (net (code "47") (name "Net-(LED6-DO)") (class "Default")
      (node (ref "LED6") (pin "3") (pinfunction "DO_3") (pintype "output"))
      (node (ref "LED7") (pin "1") (pinfunction "DI_1") (pintype "input"))
    )
    (net (code "48") (name "Net-(LED7-DO)") (class "Default")
      (node (ref "LED7") (pin "3") (pinfunction "DO_3") (pintype "output"))
      (node (ref "LED8") (pin "1") (pinfunction "DI_1") (pintype "input"))
    )
    (net (code "49") (name "Net-(LED8-DO)") (class "Default")
      (node (ref "LED8") (pin "3") (pinfunction "DO_3") (pintype "output"))
      (node (ref "LED9") (pin "1") (pinfunction "DI_1") (pintype "input"))
    )
    (net (code "50") (name "Net-(LED10-DI)") (class "Default")
      (node (ref "LED10") (pin "1") (pinfunction "DI_1") (pintype "input"))
      (node (ref "LED9") (pin "3") (pinfunction "DO_3") (pintype "output"))
    )
    (net (code "51") (name "Net-(LED10-DO)") (class "Default")
      (node (ref "LED10") (pin "3") (pinfunction "DO_3") (pintype "output"))
      (node (ref "LED12") (pin "1") (pinfunction "DI_1") (pintype "input"))
    )
    (net (code "52") (name "Net-(LED11-DI)") (class "Default")
      (node (ref "LED11") (pin "1") (pinfunction "DI_1") (pintype "input"))
      (node (ref "LED12") (pin "3") (pinfunction "DO_3") (pintype "output"))
    )
    (net (code "53") (name "Net-(LED11-DO)") (class "Default")
      (node (ref "LED11") (pin "3") (pinfunction "DO_3") (pintype "output"))
      (node (ref "LED13") (pin "1") (pinfunction "DI_1") (pintype "input"))
    )
    (net (code "54") (name "Net-(LED13-DO)") (class "Default")
      (node (ref "LED13") (pin "3") (pinfunction "DO_3") (pintype "output"))
      (node (ref "LED14") (pin "1") (pinfunction "DI_1") (pintype "input"))
    )
    (net (code "55") (name "Net-(LED14-DO)") (class "Default")
      (node (ref "LED14") (pin "3") (pinfunction "DO_3") (pintype "output"))
      (node (ref "LED15") (pin "1") (pinfunction "DI_1") (pintype "input"))
    )
    (net (code "56") (name "Net-(LED15-DO)") (class "Default")
      (node (ref "LED15") (pin "3") (pinfunction "DO_3") (pintype "output"))
      (node (ref "LED16") (pin "1") (pinfunction "DI_1") (pintype "input"))
    )
    (net (code "57") (name "Net-(R6-Pad2)") (class "Default")
      (node (ref "R6") (pin "2") (pinfunction "2_2") (pintype "passive"))
      (node (ref "R8") (pin "2") (pinfunction "2_2") (pintype "passive"))
      (node (ref "SJ4") (pin "2") (pinfunction "2_2") (pintype "passive"))
    )
    (net (code "58") (name "VIN") (class "Default")
      (node (ref "C1") (pin "2") (pinfunction "2_2") (pintype "passive"))
      (node (ref "C2") (pin "2") (pinfunction "2_2") (pintype "passive"))
      (node (ref "C3") (pin "2") (pinfunction "2_2") (pintype "passive"))
      (node (ref "C4") (pin "2") (pinfunction "2_2") (pintype "passive"))
      (node (ref "IC3") (pin "5") (pinfunction "VCC_5") (pintype "power_in"))
      (node (ref "JP1") (pin "2") (pinfunction "2_2") (pintype "passive"))
      (node (ref "JP2") (pin "2") (pinfunction "2_2") (pintype "passive"))
      (node (ref "JP3") (pin "2") (pinfunction "2_2") (pintype "passive"))
      (node (ref "JP4") (pin "2") (pinfunction "2_2") (pintype "passive"))
      (node (ref "LED1") (pin "2") (pinfunction "VDD_2") (pintype "power_in"))
      (node (ref "LED10") (pin "2") (pinfunction "VDD_2") (pintype "power_in"))
      (node (ref "LED11") (pin "2") (pinfunction "VDD_2") (pintype "power_in"))
      (node (ref "LED12") (pin "2") (pinfunction "VDD_2") (pintype "power_in"))
      (node (ref "LED13") (pin "2") (pinfunction "VDD_2") (pintype "power_in"))
      (node (ref "LED14") (pin "2") (pinfunction "VDD_2") (pintype "power_in"))
      (node (ref "LED15") (pin "2") (pinfunction "VDD_2") (pintype "power_in"))
      (node (ref "LED16") (pin "2") (pinfunction "VDD_2") (pintype "power_in"))
      (node (ref "LED2") (pin "2") (pinfunction "VDD_2") (pintype "power_in"))
      (node (ref "LED3") (pin "2") (pinfunction "VDD_2") (pintype "power_in"))
      (node (ref "LED4") (pin "2") (pinfunction "VDD_2") (pintype "power_in"))
      (node (ref "LED5") (pin "2") (pinfunction "VDD_2") (pintype "power_in"))
      (node (ref "LED6") (pin "2") (pinfunction "VDD_2") (pintype "power_in"))
      (node (ref "LED7") (pin "2") (pinfunction "VDD_2") (pintype "power_in"))
      (node (ref "LED8") (pin "2") (pinfunction "VDD_2") (pintype "power_in"))
      (node (ref "LED9") (pin "2") (pinfunction "VDD_2") (pintype "power_in"))
      (node (ref "SJ4") (pin "3") (pinfunction "3_3") (pintype "passive"))
      (node (ref "U2") (pin "1") (pinfunction "IN_1") (pintype "power_in"))
      (node (ref "U2") (pin "3") (pinfunction "EN_3") (pintype "input"))
      (node (ref "X2") (pin "2") (pinfunction "V+_2") (pintype "passive"))
    )
    (net (code "59") (name "unconnected-(IC2-PA24{slash}I4{slash}SERCOM1.2-Pad21)") (class "Default")
      (node (ref "IC2") (pin "21") (pinfunction "PA24/I4/SERCOM1.2_21") (pintype "bidirectional"))
    )
    (net (code "60") (name "unconnected-(IC2-PA25{slash}I5{slash}SERCOM1.3-Pad22)") (class "Default")
      (node (ref "IC2") (pin "22") (pinfunction "PA25/I5/SERCOM1.3_22") (pintype "bidirectional"))
    )
    (net (code "61") (name "unconnected-(LED16-DO-Pad3)") (class "Default")
      (node (ref "LED16") (pin "3") (pinfunction "DO_3") (pintype "output"))
    )
    (net (code "62") (name "unconnected-(TP1-PadP$1)") (class "Default")
      (node (ref "TP1") (pin "P$1") (pinfunction "P$1_P$1") (pintype "bidirectional"))
    )
    (net (code "63") (name "unconnected-(TP2-PadP$1)") (class "Default")
      (node (ref "TP2") (pin "P$1") (pinfunction "P$1_P$1") (pintype "bidirectional"))
    )
    (net (code "64") (name "unconnected-(TP3-PadP$1)") (class "Default")
      (node (ref "TP3") (pin "P$1") (pinfunction "P$1_P$1") (pintype "bidirectional"))
    )
    (net (code "65") (name "unconnected-(TP4-PadP$1)") (class "Default")
      (node (ref "TP4") (pin "P$1") (pinfunction "P$1_P$1") (pintype "bidirectional"))
    )
    (net (code "66") (name "unconnected-(U2-P4-Pad4)") (class "Default")
      (node (ref "U2") (pin "4") (pinfunction "P4_4") (pintype "bidirectional"))
    )
  )
)
